# F3-Quad-Brushed-SIDE-USB-JMPR.net
KiCad netlist of a schematic drawn in EAGLE
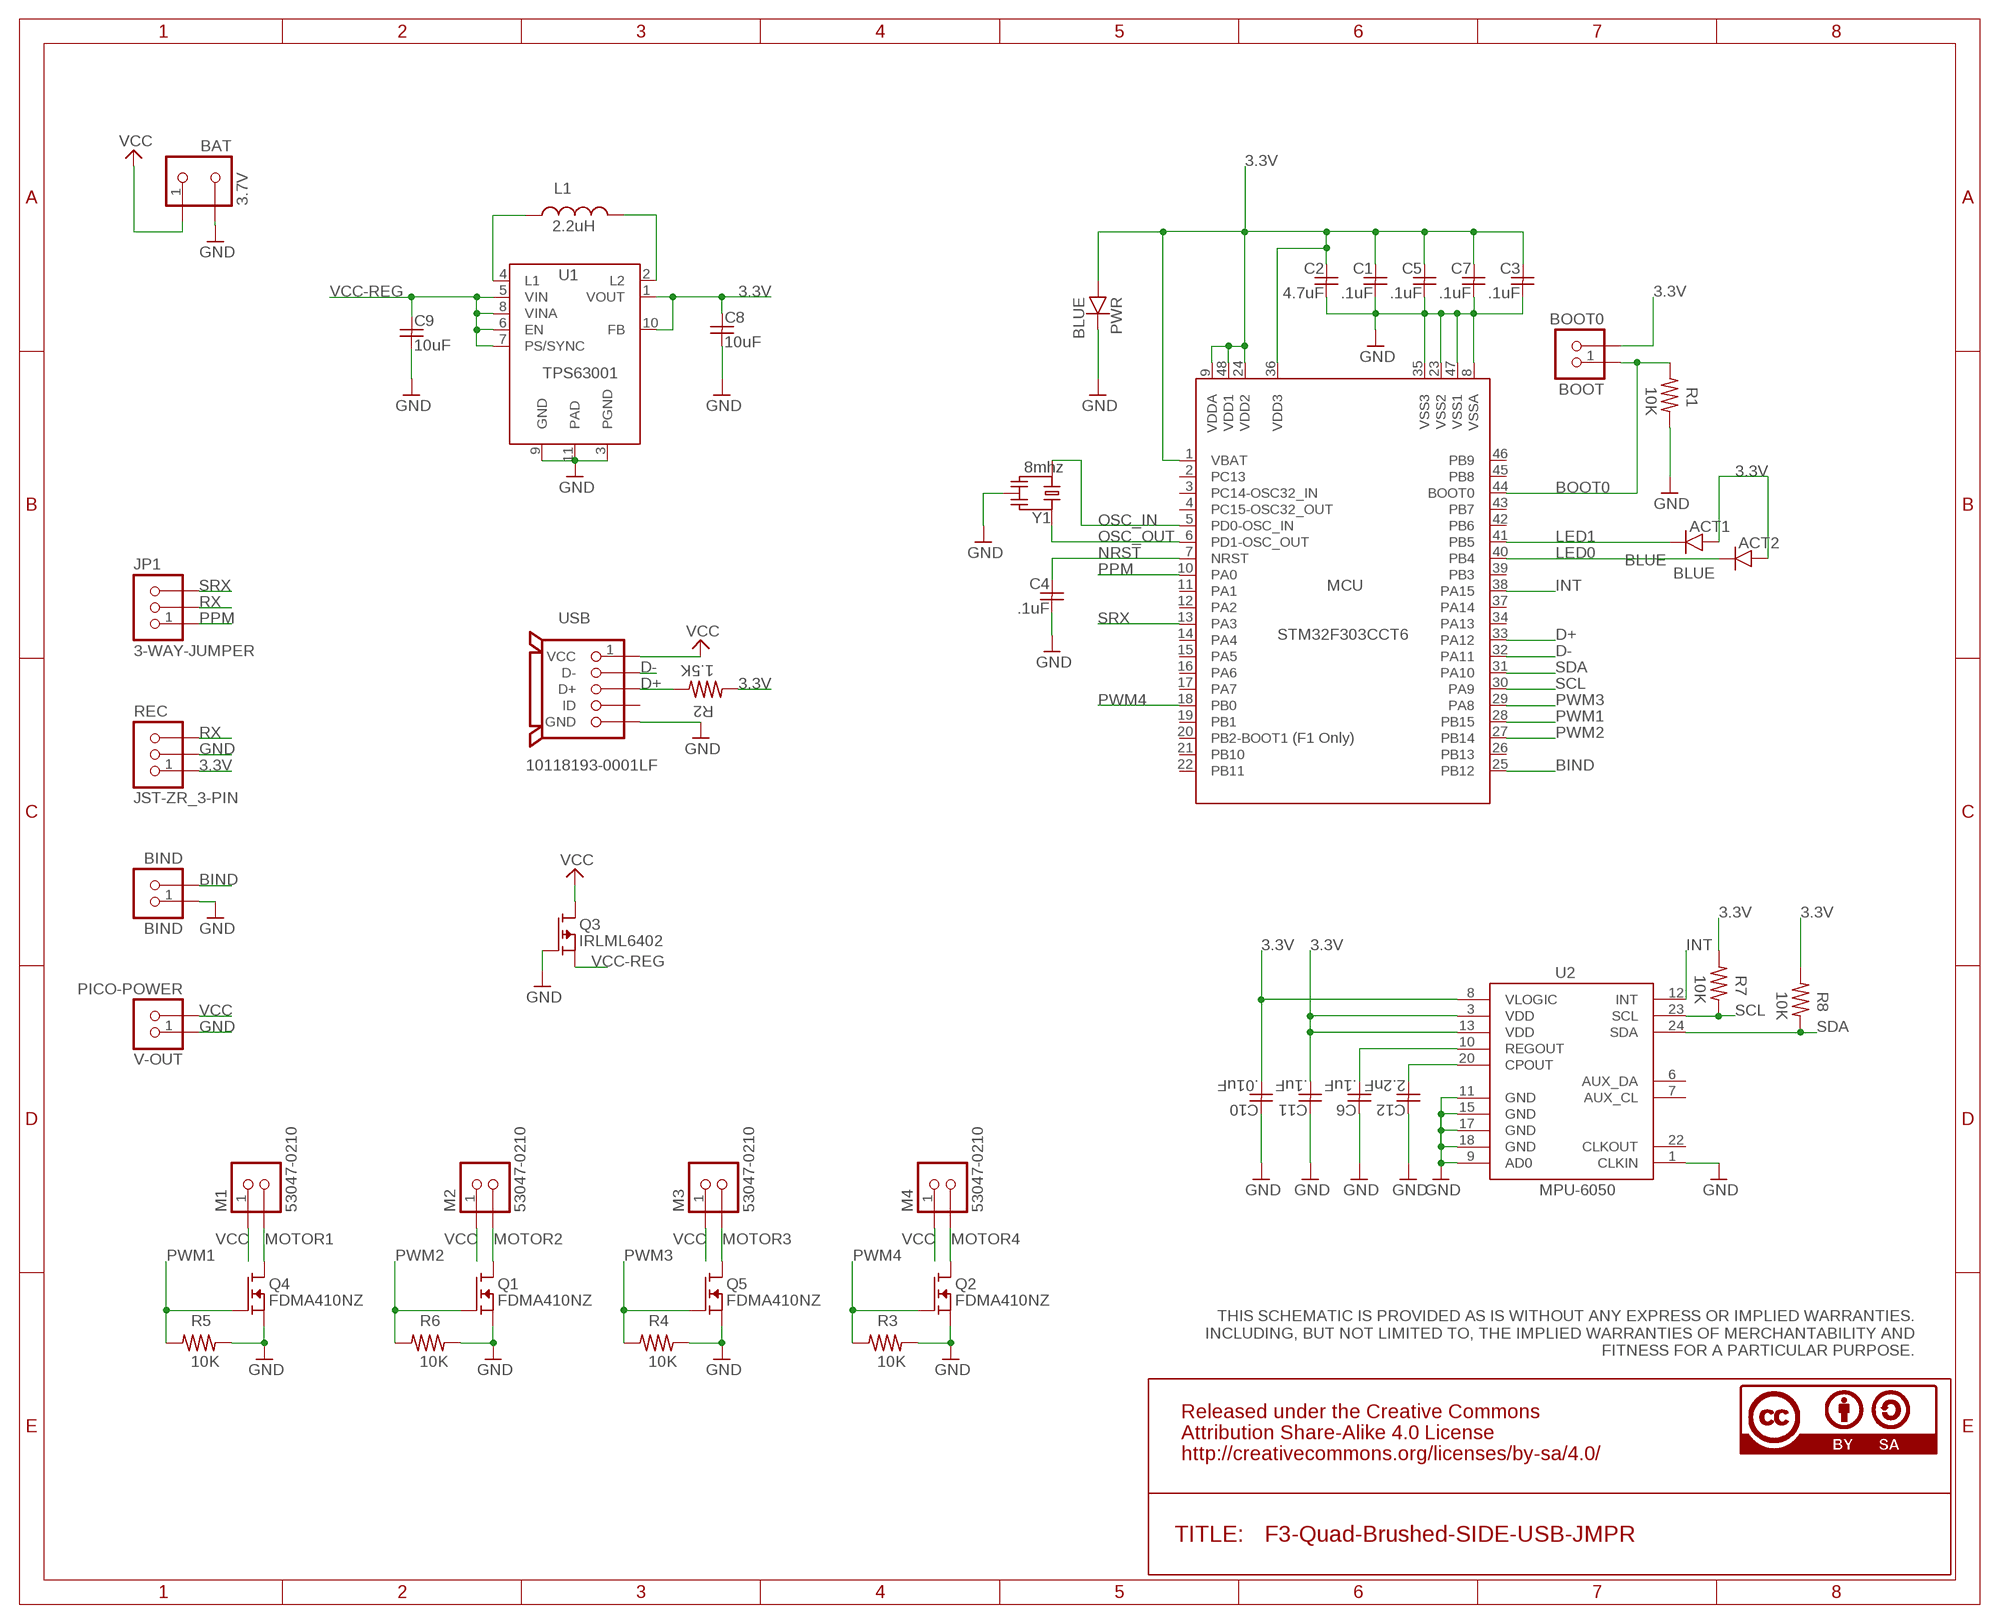
[diagram p0: schematic, sheet 1]

(export (version "E")
  (design (tool "Eeschema 10.0.6"))
  (components
    (comp (ref "ACT1")
      (value "BLUE")
      (footprint "eagle-import:SMD-CHIP-LED-0805")
      (fields (field (name "MF") "Kingbright") (field (name "MPN") "APHCM2012QBC/D-F01"))
      (libsource (lib "eagle-import") (part "SMD-CHIP-LED-0805"))
    )
    (comp (ref "ACT2")
      (value "BLUE")
      (footprint "eagle-import:SMD-CHIP-LED-0805")
      (fields (field (name "MF") "Kingbright") (field (name "MPN") "APHCM2012QBC/D-F01"))
      (libsource (lib "eagle-import") (part "SMD-CHIP-LED-0805"))
    )
    (comp (ref "BAT")
      (value "3.7V")
      (footprint "eagle-import:S2B-PH-K-S")
      (fields (field (name "MF") "JST") (field (name "MPN") "S2B-PH-K-S"))
      (libsource (lib "eagle-import") (part "JST-PH-BAT"))
    )
    (comp (ref "BIND")
      (value "BIND")
      (footprint "eagle-import:1.27MM-PINHEADX2")
      (fields (field (name "MF") "Sullins") (field (name "MPN") "GRPB021VWVN-RC (JUMPER IS M50-1930005)"))
      (libsource (lib "eagle-import") (part "1.27MM-PINHEADX2"))
    )
    (comp (ref "BOOT")
      (value "BOOT0")
      (footprint "eagle-import:1.27MM-PINHEADX2")
      (fields (field (name "MF") "Sullins") (field (name "MPN") "GRPB021VWVN-RC (JUMPER IS M50-1930005)"))
      (libsource (lib "eagle-import") (part "1.27MM-PINHEADX2"))
    )
    (comp (ref "C1")
      (value ".1uF")
      (footprint "eagle-import:MUR-CAP-0603")
      (fields (field (name "MF") "Murata") (field (name "MPN") "GRM188R71C104KA01D"))
      (libsource (lib "eagle-import") (part "CAPACITOR.1UF"))
    )
    (comp (ref "C2")
      (value "4.7uF")
      (footprint "eagle-import:MUR-CAP-0603")
      (fields (field (name "MF") "Murata") (field (name "MPN") "GRJ188C70J475KE11D"))
      (libsource (lib "eagle-import") (part "CAPACITOR4.7UF"))
    )
    (comp (ref "C3")
      (value ".1uF")
      (footprint "eagle-import:MUR-CAP-0603")
      (fields (field (name "MF") "Murata") (field (name "MPN") "GRM188R71C104KA01D"))
      (libsource (lib "eagle-import") (part "CAPACITOR.1UF"))
    )
    (comp (ref "C4")
      (value ".1uF")
      (footprint "eagle-import:MUR-CAP-0603")
      (fields (field (name "MF") "Murata") (field (name "MPN") "GRM188R71C104KA01D"))
      (libsource (lib "eagle-import") (part "CAPACITOR.1UF"))
    )
    (comp (ref "C5")
      (value ".1uF")
      (footprint "eagle-import:MUR-CAP-0603")
      (fields (field (name "MF") "Murata") (field (name "MPN") "GRM188R71C104KA01D"))
      (libsource (lib "eagle-import") (part "CAPACITOR.1UF"))
    )
    (comp (ref "C6")
      (value ".1uF")
      (footprint "eagle-import:MUR-CAP-0603")
      (fields (field (name "MF") "Murata") (field (name "MPN") "GRM188R71C104KA01D"))
      (libsource (lib "eagle-import") (part "CAPACITOR.1UF"))
    )
    (comp (ref "C7")
      (value ".1uF")
      (footprint "eagle-import:MUR-CAP-0603")
      (fields (field (name "MF") "Murata") (field (name "MPN") "GRM188R71C104KA01D"))
      (libsource (lib "eagle-import") (part "CAPACITOR.1UF"))
    )
    (comp (ref "C8")
      (value "10uF")
      (footprint "eagle-import:YUDEN-CAP-0805")
      (fields (field (name "MF") "Taiyo Yuden") (field (name "MPN") "JMK212AB7106KG-T"))
      (libsource (lib "eagle-import") (part "CAPACITOR10UF"))
    )
    (comp (ref "C9")
      (value "10uF")
      (footprint "eagle-import:YUDEN-CAP-0805")
      (fields (field (name "MF") "Taiyo Yuden") (field (name "MPN") "JMK212AB7106KG-T"))
      (libsource (lib "eagle-import") (part "CAPACITOR10UF"))
    )
    (comp (ref "C10")
      (value ".01uF")
      (footprint "eagle-import:MUR-CAP-0603")
      (fields (field (name "MF") "Murata") (field (name "MPN") "GRM188R71C103KA01D"))
      (libsource (lib "eagle-import") (part "CAPACITOR.01UF"))
    )
    (comp (ref "C11")
      (value ".1uF")
      (footprint "eagle-import:MUR-CAP-0603")
      (fields (field (name "MF") "Murata") (field (name "MPN") "GRM188R71C104KA01D"))
      (libsource (lib "eagle-import") (part "CAPACITOR.1UF"))
    )
    (comp (ref "C12")
      (value "2.2nF")
      (footprint "eagle-import:MUR-CAP-0603")
      (fields (field (name "MF") "Murata") (field (name "MPN") "GRM188R71C222KA01D"))
      (libsource (lib "eagle-import") (part "CAPACITOR2.2NF"))
    )
    (comp (ref "JP1")
      (value "3-WAY-JUMPER")
      (footprint "eagle-import:3-WAY-JUMPER")
      (libsource (lib "eagle-import") (part "3-WAY-JUMPER"))
    )
    (comp (ref "L1")
      (value "2.2uH")
      (footprint "eagle-import:NR301X")
      (fields (field (name "MF") "Taiyo Yuden") (field (name "MPN") "NR3015T2R2M"))
      (libsource (lib "eagle-import") (part "NR301X"))
    )
    (comp (ref "M1")
      (value "53047-0210")
      (footprint "eagle-import:PICO-53047-02")
      (fields (field (name "MF") "MOLEX"))
      (libsource (lib "eagle-import") (part "PICO-1.25-MOTOR"))
    )
    (comp (ref "M2")
      (value "53047-0210")
      (footprint "eagle-import:PICO-53047-02")
      (fields (field (name "MF") "MOLEX"))
      (libsource (lib "eagle-import") (part "PICO-1.25-MOTOR"))
    )
    (comp (ref "M3")
      (value "53047-0210")
      (footprint "eagle-import:PICO-53047-02")
      (fields (field (name "MF") "MOLEX"))
      (libsource (lib "eagle-import") (part "PICO-1.25-MOTOR"))
    )
    (comp (ref "M4")
      (value "53047-0210")
      (footprint "eagle-import:PICO-53047-02")
      (fields (field (name "MF") "MOLEX"))
      (libsource (lib "eagle-import") (part "PICO-1.25-MOTOR"))
    )
    (comp (ref "MCU")
      (value "STM32F303CCT6")
      (footprint "eagle-import:LQFP48-7X7")
      (fields (field (name "MF") "ST"))
      (libsource (lib "eagle-import") (part "STM32FX03-F3"))
    )
    (comp (ref "PWR")
      (value "BLUE")
      (footprint "eagle-import:SMD-CHIP-LED-0805")
      (fields (field (name "MF") "Kingbright") (field (name "MPN") "APHCM2012QBC/D-F01"))
      (libsource (lib "eagle-import") (part "SMD-CHIP-LED-0805"))
    )
    (comp (ref "Q1")
      (value "FDMA410NZ")
      (footprint "eagle-import:MICROFET-2X2")
      (fields (field (name "MF") "Fairchild"))
      (libsource (lib "eagle-import") (part "FDMA410NZ"))
    )
    (comp (ref "Q2")
      (value "FDMA410NZ")
      (footprint "eagle-import:MICROFET-2X2")
      (fields (field (name "MF") "Fairchild"))
      (libsource (lib "eagle-import") (part "FDMA410NZ"))
    )
    (comp (ref "Q3")
      (value "IRLML6402")
      (footprint "eagle-import:SOT-23")
      (fields (field (name "MF") "IR"))
      (libsource (lib "eagle-import") (part "MOSFET-P"))
    )
    (comp (ref "Q4")
      (value "FDMA410NZ")
      (footprint "eagle-import:MICROFET-2X2")
      (fields (field (name "MF") "Fairchild"))
      (libsource (lib "eagle-import") (part "FDMA410NZ"))
    )
    (comp (ref "Q5")
      (value "FDMA410NZ")
      (footprint "eagle-import:MICROFET-2X2")
      (fields (field (name "MF") "Fairchild"))
      (libsource (lib "eagle-import") (part "FDMA410NZ"))
    )
    (comp (ref "R1")
      (value "10K")
      (footprint "eagle-import:VISH-RES-0603")
      (fields (field (name "MF") "Vishay") (field (name "MPN") "CRCW060310K0FKEAHP"))
      (libsource (lib "eagle-import") (part "RESISTOR10K"))
    )
    (comp (ref "R2")
      (value "1.5K")
      (footprint "eagle-import:VISH-RES-0603")
      (fields (field (name "MF") "Vishay") (field (name "MPN") "CRCW06031K50FKEAHP"))
      (libsource (lib "eagle-import") (part "RESISTOR1.5K"))
    )
    (comp (ref "R3")
      (value "10K")
      (footprint "eagle-import:VISH-RES-0603")
      (fields (field (name "MF") "Vishay") (field (name "MPN") "CRCW060310K0FKEAHP"))
      (libsource (lib "eagle-import") (part "RESISTOR10K"))
    )
    (comp (ref "R4")
      (value "10K")
      (footprint "eagle-import:VISH-RES-0603")
      (fields (field (name "MF") "Vishay") (field (name "MPN") "CRCW060310K0FKEAHP"))
      (libsource (lib "eagle-import") (part "RESISTOR10K"))
    )
    (comp (ref "R5")
      (value "10K")
      (footprint "eagle-import:VISH-RES-0603")
      (fields (field (name "MF") "Vishay") (field (name "MPN") "CRCW060310K0FKEAHP"))
      (libsource (lib "eagle-import") (part "RESISTOR10K"))
    )
    (comp (ref "R6")
      (value "10K")
      (footprint "eagle-import:VISH-RES-0603")
      (fields (field (name "MF") "Vishay") (field (name "MPN") "CRCW060310K0FKEAHP"))
      (libsource (lib "eagle-import") (part "RESISTOR10K"))
    )
    (comp (ref "R7")
      (value "10K")
      (footprint "eagle-import:VISH-RES-0603")
      (fields (field (name "MF") "Vishay") (field (name "MPN") "CRCW060310K0FKEAHP"))
      (libsource (lib "eagle-import") (part "RESISTOR10K"))
    )
    (comp (ref "R8")
      (value "10K")
      (footprint "eagle-import:VISH-RES-0603")
      (fields (field (name "MF") "Vishay") (field (name "MPN") "CRCW060310K0FKEAHP"))
      (libsource (lib "eagle-import") (part "RESISTOR10K"))
    )
    (comp (ref "REC")
      (value "JST-ZR_3-PIN")
      (footprint "eagle-import:S3B-ZR")
      (fields (field (name "MF") "JST") (field (name "MPN") "S3B-ZR"))
      (libsource (lib "eagle-import") (part "JST-ZR_3-PIN"))
    )
    (comp (ref "U1")
      (value "TPS63001")
      (footprint "eagle-import:VSON-N10")
      (fields (field (name "MF") "TI") (field (name "MPN") "TPS63001DRCR"))
      (libsource (lib "eagle-import") (part "TPS630XX-TPS63001"))
    )
    (comp (ref "U2")
      (value "MPU-6050")
      (footprint "eagle-import:QFN24-4X4")
      (fields (field (name "MF") "Invensense"))
      (libsource (lib "eagle-import") (part "MPU-6050"))
    )
    (comp (ref "USB")
      (value "10118193-0001LF")
      (footprint "eagle-import:10118193-0001LF")
      (fields (field (name "MF") "FCI"))
      (libsource (lib "eagle-import") (part "USB-MICRO-B-FCI"))
    )
    (comp (ref "V-OUT")
      (value "PICO-POWER")
      (footprint "eagle-import:PICO_1.25_.5MM")
      (fields (field (name "MF") "Molex") (field (name "MPN") "53047-0210"))
      (libsource (lib "eagle-import") (part "PICO-POWER"))
    )
    (comp (ref "Y1")
      (value "8mhz")
      (footprint "eagle-import:RESONATOR_8")
      (fields (field (name "MF") "Murata") (field (name "MPN") "CSTCE8M00G55-R0"))
      (libsource (lib "eagle-import") (part "RESONATOR8MHZ"))
    )
  )
  (nets
    (net (code "1") (name "/3.3V") (class "Default")
      (node (ref "ACT1") (pin "A") (pinfunction "A_A") (pintype "passive"))
      (node (ref "ACT2") (pin "A") (pinfunction "A_A") (pintype "passive"))
      (node (ref "BOOT") (pin "2") (pinfunction "2_2") (pintype "passive"))
      (node (ref "C1") (pin "1") (pinfunction "1_1") (pintype "passive"))
      (node (ref "C10") (pin "2") (pinfunction "2_2") (pintype "passive"))
      (node (ref "C11") (pin "2") (pinfunction "2_2") (pintype "passive"))
      (node (ref "C2") (pin "1") (pinfunction "1_1") (pintype "passive"))
      (node (ref "C3") (pin "1") (pinfunction "1_1") (pintype "passive"))
      (node (ref "C5") (pin "1") (pinfunction "1_1") (pintype "passive"))
      (node (ref "C7") (pin "1") (pinfunction "1_1") (pintype "passive"))
      (node (ref "C8") (pin "1") (pinfunction "1_1") (pintype "passive"))
      (node (ref "MCU") (pin "1") (pinfunction "VBAT_1") (pintype "bidirectional"))
      (node (ref "MCU") (pin "24") (pinfunction "VDD2_24") (pintype "bidirectional"))
      (node (ref "MCU") (pin "36") (pinfunction "VDD3_36") (pintype "bidirectional"))
      (node (ref "MCU") (pin "48") (pinfunction "VDD1_48") (pintype "bidirectional"))
      (node (ref "MCU") (pin "9") (pinfunction "VDDA_9") (pintype "bidirectional"))
      (node (ref "PWR") (pin "A") (pinfunction "A_A") (pintype "passive"))
      (node (ref "R2") (pin "2") (pinfunction "2_2") (pintype "passive"))
      (node (ref "R7") (pin "2") (pinfunction "2_2") (pintype "passive"))
      (node (ref "R8") (pin "2") (pinfunction "2_2") (pintype "passive"))
      (node (ref "REC") (pin "1") (pinfunction "1_1") (pintype "bidirectional"))
      (node (ref "U1") (pin "1") (pinfunction "VOUT_1") (pintype "bidirectional"))
      (node (ref "U1") (pin "10") (pinfunction "FB_10") (pintype "bidirectional"))
      (node (ref "U2") (pin "13") (pinfunction "VDD_13") (pintype "bidirectional"))
      (node (ref "U2") (pin "3") (pinfunction "VDD_3") (pintype "bidirectional"))
      (node (ref "U2") (pin "8") (pinfunction "VLOGIC_8") (pintype "bidirectional"))
    )
    (net (code "2") (name "/BIND") (class "Default")
      (node (ref "BIND") (pin "2") (pinfunction "2_2") (pintype "passive"))
      (node (ref "MCU") (pin "25") (pinfunction "PB12_25") (pintype "bidirectional"))
    )
    (net (code "3") (name "/BOOT0") (class "Default")
      (node (ref "BOOT") (pin "1") (pinfunction "1_1") (pintype "passive"))
      (node (ref "MCU") (pin "44") (pinfunction "BOOT0_44") (pintype "bidirectional"))
      (node (ref "R1") (pin "2") (pinfunction "2_2") (pintype "passive"))
    )
    (net (code "4") (name "/D+") (class "Default")
      (node (ref "MCU") (pin "33") (pinfunction "PA12_33") (pintype "bidirectional"))
      (node (ref "R2") (pin "1") (pinfunction "1_1") (pintype "passive"))
      (node (ref "USB") (pin "3") (pinfunction "D+_3") (pintype "passive"))
    )
    (net (code "5") (name "/D-") (class "Default")
      (node (ref "MCU") (pin "32") (pinfunction "PA11_32") (pintype "bidirectional"))
      (node (ref "USB") (pin "2") (pinfunction "D-_2") (pintype "passive"))
    )
    (net (code "6") (name "/INT") (class "Default")
      (node (ref "MCU") (pin "38") (pinfunction "PA15_38") (pintype "bidirectional"))
      (node (ref "U2") (pin "12") (pinfunction "INT_12") (pintype "bidirectional"))
    )
    (net (code "7") (name "/LED0") (class "Default")
      (node (ref "ACT2") (pin "C") (pinfunction "C_C") (pintype "passive"))
      (node (ref "MCU") (pin "40") (pinfunction "PB4_40") (pintype "bidirectional"))
    )
    (net (code "8") (name "/LED1") (class "Default")
      (node (ref "ACT1") (pin "C") (pinfunction "C_C") (pintype "passive"))
      (node (ref "MCU") (pin "41") (pinfunction "PB5_41") (pintype "bidirectional"))
    )
    (net (code "9") (name "/MOTOR1") (class "Default")
      (node (ref "M1") (pin "2") (pinfunction "2_2") (pintype "passive"))
      (node (ref "Q4") (pin "D") (pinfunction "D_D") (pintype "bidirectional"))
      (node (ref "Q4") (pin "D1") (pinfunction "D_D1") (pintype "bidirectional"))
      (node (ref "Q4") (pin "D2") (pinfunction "D_D2") (pintype "bidirectional"))
      (node (ref "Q4") (pin "D3") (pinfunction "D_D3") (pintype "bidirectional"))
      (node (ref "Q4") (pin "D4") (pinfunction "D_D4") (pintype "bidirectional"))
    )
    (net (code "10") (name "/MOTOR2") (class "Default")
      (node (ref "M2") (pin "2") (pinfunction "2_2") (pintype "passive"))
      (node (ref "Q1") (pin "D") (pinfunction "D_D") (pintype "bidirectional"))
      (node (ref "Q1") (pin "D1") (pinfunction "D_D1") (pintype "bidirectional"))
      (node (ref "Q1") (pin "D2") (pinfunction "D_D2") (pintype "bidirectional"))
      (node (ref "Q1") (pin "D3") (pinfunction "D_D3") (pintype "bidirectional"))
      (node (ref "Q1") (pin "D4") (pinfunction "D_D4") (pintype "bidirectional"))
    )
    (net (code "11") (name "/MOTOR3") (class "Default")
      (node (ref "M3") (pin "2") (pinfunction "2_2") (pintype "passive"))
      (node (ref "Q5") (pin "D") (pinfunction "D_D") (pintype "bidirectional"))
      (node (ref "Q5") (pin "D1") (pinfunction "D_D1") (pintype "bidirectional"))
      (node (ref "Q5") (pin "D2") (pinfunction "D_D2") (pintype "bidirectional"))
      (node (ref "Q5") (pin "D3") (pinfunction "D_D3") (pintype "bidirectional"))
      (node (ref "Q5") (pin "D4") (pinfunction "D_D4") (pintype "bidirectional"))
    )
    (net (code "12") (name "/MOTOR4") (class "Default")
      (node (ref "M4") (pin "2") (pinfunction "2_2") (pintype "passive"))
      (node (ref "Q2") (pin "D") (pinfunction "D_D") (pintype "bidirectional"))
      (node (ref "Q2") (pin "D1") (pinfunction "D_D1") (pintype "bidirectional"))
      (node (ref "Q2") (pin "D2") (pinfunction "D_D2") (pintype "bidirectional"))
      (node (ref "Q2") (pin "D3") (pinfunction "D_D3") (pintype "bidirectional"))
      (node (ref "Q2") (pin "D4") (pinfunction "D_D4") (pintype "bidirectional"))
    )
    (net (code "13") (name "/NRST") (class "Default")
      (node (ref "C4") (pin "1") (pinfunction "1_1") (pintype "passive"))
      (node (ref "MCU") (pin "7") (pinfunction "NRST_7") (pintype "bidirectional"))
    )
    (net (code "14") (name "/OSC_IN") (class "Default")
      (node (ref "MCU") (pin "5") (pinfunction "PD0-OSC_IN_5") (pintype "bidirectional"))
      (node (ref "Y1") (pin "3") (pinfunction "3_3") (pintype "passive"))
    )
    (net (code "15") (name "/OSC_OUT") (class "Default")
      (node (ref "MCU") (pin "6") (pinfunction "PD1-OSC_OUT_6") (pintype "bidirectional"))
      (node (ref "Y1") (pin "1") (pinfunction "1_1") (pintype "passive"))
    )
    (net (code "16") (name "/PPM") (class "Default")
      (node (ref "JP1") (pin "1") (pinfunction "1_1") (pintype "bidirectional"))
      (node (ref "MCU") (pin "10") (pinfunction "PA0_10") (pintype "bidirectional"))
    )
    (net (code "17") (name "/PWM1") (class "Default")
      (node (ref "MCU") (pin "28") (pinfunction "PB15_28") (pintype "bidirectional"))
      (node (ref "Q4") (pin "G") (pinfunction "G_G") (pintype "bidirectional"))
      (node (ref "R5") (pin "2") (pinfunction "2_2") (pintype "passive"))
    )
    (net (code "18") (name "/PWM2") (class "Default")
      (node (ref "MCU") (pin "27") (pinfunction "PB14_27") (pintype "bidirectional"))
      (node (ref "Q1") (pin "G") (pinfunction "G_G") (pintype "bidirectional"))
      (node (ref "R6") (pin "2") (pinfunction "2_2") (pintype "passive"))
    )
    (net (code "19") (name "/PWM3") (class "Default")
      (node (ref "MCU") (pin "29") (pinfunction "PA8_29") (pintype "bidirectional"))
      (node (ref "Q5") (pin "G") (pinfunction "G_G") (pintype "bidirectional"))
      (node (ref "R4") (pin "2") (pinfunction "2_2") (pintype "passive"))
    )
    (net (code "20") (name "/PWM4") (class "Default")
      (node (ref "MCU") (pin "18") (pinfunction "PB0_18") (pintype "bidirectional"))
      (node (ref "Q2") (pin "G") (pinfunction "G_G") (pintype "bidirectional"))
      (node (ref "R3") (pin "2") (pinfunction "2_2") (pintype "passive"))
    )
    (net (code "21") (name "/RX") (class "Default")
      (node (ref "JP1") (pin "2") (pinfunction "2_2") (pintype "bidirectional"))
      (node (ref "REC") (pin "3") (pinfunction "3_3") (pintype "bidirectional"))
    )
    (net (code "22") (name "/SCL") (class "Default")
      (node (ref "MCU") (pin "30") (pinfunction "PA9_30") (pintype "bidirectional"))
      (node (ref "R7") (pin "1") (pinfunction "1_1") (pintype "passive"))
      (node (ref "U2") (pin "23") (pinfunction "SCL_23") (pintype "bidirectional"))
    )
    (net (code "23") (name "/SDA") (class "Default")
      (node (ref "MCU") (pin "31") (pinfunction "PA10_31") (pintype "bidirectional"))
      (node (ref "R8") (pin "1") (pinfunction "1_1") (pintype "passive"))
      (node (ref "U2") (pin "24") (pinfunction "SDA_24") (pintype "bidirectional"))
    )
    (net (code "24") (name "/SRX") (class "Default")
      (node (ref "JP1") (pin "3") (pinfunction "3_3") (pintype "bidirectional"))
      (node (ref "MCU") (pin "13") (pinfunction "PA3_13") (pintype "bidirectional"))
    )
    (net (code "25") (name "/VCC-REG") (class "Default")
      (node (ref "C9") (pin "1") (pinfunction "1_1") (pintype "passive"))
      (node (ref "Q3") (pin "2") (pinfunction "S_2") (pintype "bidirectional"))
      (node (ref "U1") (pin "5") (pinfunction "VIN_5") (pintype "bidirectional"))
      (node (ref "U1") (pin "6") (pinfunction "EN_6") (pintype "bidirectional"))
      (node (ref "U1") (pin "7") (pinfunction "PS/SYNC_7") (pintype "bidirectional"))
      (node (ref "U1") (pin "8") (pinfunction "VINA_8") (pintype "bidirectional"))
    )
    (net (code "26") (name "GND") (class "Default")
      (node (ref "BAT") (pin "2") (pinfunction "2_2") (pintype "bidirectional"))
      (node (ref "BIND") (pin "1") (pinfunction "1_1") (pintype "passive"))
      (node (ref "C1") (pin "2") (pinfunction "2_2") (pintype "passive"))
      (node (ref "C10") (pin "1") (pinfunction "1_1") (pintype "passive"))
      (node (ref "C11") (pin "1") (pinfunction "1_1") (pintype "passive"))
      (node (ref "C12") (pin "1") (pinfunction "1_1") (pintype "passive"))
      (node (ref "C2") (pin "2") (pinfunction "2_2") (pintype "passive"))
      (node (ref "C3") (pin "2") (pinfunction "2_2") (pintype "passive"))
      (node (ref "C4") (pin "2") (pinfunction "2_2") (pintype "passive"))
      (node (ref "C5") (pin "2") (pinfunction "2_2") (pintype "passive"))
      (node (ref "C6") (pin "1") (pinfunction "1_1") (pintype "passive"))
      (node (ref "C7") (pin "2") (pinfunction "2_2") (pintype "passive"))
      (node (ref "C8") (pin "2") (pinfunction "2_2") (pintype "passive"))
      (node (ref "C9") (pin "2") (pinfunction "2_2") (pintype "passive"))
      (node (ref "MCU") (pin "23") (pinfunction "VSS2_23") (pintype "bidirectional"))
      (node (ref "MCU") (pin "35") (pinfunction "VSS3_35") (pintype "bidirectional"))
      (node (ref "MCU") (pin "47") (pinfunction "VSS1_47") (pintype "bidirectional"))
      (node (ref "MCU") (pin "8") (pinfunction "VSSA_8") (pintype "bidirectional"))
      (node (ref "PWR") (pin "C") (pinfunction "C_C") (pintype "passive"))
      (node (ref "Q1") (pin "S") (pinfunction "S_S") (pintype "bidirectional"))
      (node (ref "Q1") (pin "S1") (pinfunction "S_S1") (pintype "bidirectional"))
      (node (ref "Q2") (pin "S") (pinfunction "S_S") (pintype "bidirectional"))
      (node (ref "Q2") (pin "S1") (pinfunction "S_S1") (pintype "bidirectional"))
      (node (ref "Q3") (pin "1") (pinfunction "G_1") (pintype "bidirectional"))
      (node (ref "Q4") (pin "S") (pinfunction "S_S") (pintype "bidirectional"))
      (node (ref "Q4") (pin "S1") (pinfunction "S_S1") (pintype "bidirectional"))
      (node (ref "Q5") (pin "S") (pinfunction "S_S") (pintype "bidirectional"))
      (node (ref "Q5") (pin "S1") (pinfunction "S_S1") (pintype "bidirectional"))
      (node (ref "R1") (pin "1") (pinfunction "1_1") (pintype "passive"))
      (node (ref "R3") (pin "1") (pinfunction "1_1") (pintype "passive"))
      (node (ref "R4") (pin "1") (pinfunction "1_1") (pintype "passive"))
      (node (ref "R5") (pin "1") (pinfunction "1_1") (pintype "passive"))
      (node (ref "R6") (pin "1") (pinfunction "1_1") (pintype "passive"))
      (node (ref "REC") (pin "2") (pinfunction "2_2") (pintype "bidirectional"))
      (node (ref "U1") (pin "11") (pinfunction "PAD_11") (pintype "bidirectional"))
      (node (ref "U1") (pin "3") (pinfunction "PGND_3") (pintype "bidirectional"))
      (node (ref "U1") (pin "9") (pinfunction "GND_9") (pintype "bidirectional"))
      (node (ref "U2") (pin "1") (pinfunction "CLKIN_1") (pintype "bidirectional"))
      (node (ref "U2") (pin "11") (pinfunction "GND_11") (pintype "bidirectional"))
      (node (ref "U2") (pin "15") (pinfunction "GND_15") (pintype "bidirectional"))
      (node (ref "U2") (pin "17") (pinfunction "GND_17") (pintype "bidirectional"))
      (node (ref "U2") (pin "18") (pinfunction "GND_18") (pintype "bidirectional"))
      (node (ref "U2") (pin "9") (pinfunction "AD0_9") (pintype "bidirectional"))
      (node (ref "USB") (pin "5") (pinfunction "GND_5") (pintype "passive"))
      (node (ref "USB") (pin "GND") (pinfunction "GND_GND") (pintype "passive"))
      (node (ref "USB") (pin "GND2") (pinfunction "GND_GND2") (pintype "passive"))
      (node (ref "USB") (pin "HOLE1") (pinfunction "GND_HOLE1") (pintype "passive"))
      (node (ref "USB") (pin "HOLE2") (pinfunction "GND_HOLE2") (pintype "passive"))
      (node (ref "V-OUT") (pin "1") (pinfunction "1_1") (pintype "passive"))
      (node (ref "Y1") (pin "2") (pinfunction "2_2") (pintype "passive"))
    )
    (net (code "27") (name "Net-(U1-L1)") (class "Default")
      (node (ref "L1") (pin "1") (pinfunction "1_1") (pintype "passive"))
      (node (ref "U1") (pin "4") (pinfunction "L1_4") (pintype "bidirectional"))
    )
    (net (code "28") (name "Net-(U1-L2)") (class "Default")
      (node (ref "L1") (pin "2") (pinfunction "2_2") (pintype "passive"))
      (node (ref "U1") (pin "2") (pinfunction "L2_2") (pintype "bidirectional"))
    )
    (net (code "29") (name "Net-(U2-CPOUT)") (class "Default")
      (node (ref "C12") (pin "2") (pinfunction "2_2") (pintype "passive"))
      (node (ref "U2") (pin "20") (pinfunction "CPOUT_20") (pintype "bidirectional"))
    )
    (net (code "30") (name "Net-(U2-REGOUT)") (class "Default")
      (node (ref "C6") (pin "2") (pinfunction "2_2") (pintype "passive"))
      (node (ref "U2") (pin "10") (pinfunction "REGOUT_10") (pintype "bidirectional"))
    )
    (net (code "31") (name "VCC") (class "Default")
      (node (ref "BAT") (pin "1") (pinfunction "1_1") (pintype "bidirectional"))
      (node (ref "M1") (pin "1") (pinfunction "1_1") (pintype "passive"))
      (node (ref "M2") (pin "1") (pinfunction "1_1") (pintype "passive"))
      (node (ref "M3") (pin "1") (pinfunction "1_1") (pintype "passive"))
      (node (ref "M4") (pin "1") (pinfunction "1_1") (pintype "passive"))
      (node (ref "Q3") (pin "3") (pinfunction "D_3") (pintype "bidirectional"))
      (node (ref "USB") (pin "1") (pinfunction "VCC_1") (pintype "passive"))
      (node (ref "V-OUT") (pin "2") (pinfunction "2_2") (pintype "passive"))
    )
    (net (code "32") (name "unconnected-(MCU-PA1-Pad11)") (class "Default")
      (node (ref "MCU") (pin "11") (pinfunction "PA1_11") (pintype "bidirectional"))
    )
    (net (code "33") (name "unconnected-(MCU-PA2-Pad12)") (class "Default")
      (node (ref "MCU") (pin "12") (pinfunction "PA2_12") (pintype "bidirectional"))
    )
    (net (code "34") (name "unconnected-(MCU-PA4-Pad14)") (class "Default")
      (node (ref "MCU") (pin "14") (pinfunction "PA4_14") (pintype "bidirectional"))
    )
    (net (code "35") (name "unconnected-(MCU-PA5-Pad15)") (class "Default")
      (node (ref "MCU") (pin "15") (pinfunction "PA5_15") (pintype "bidirectional"))
    )
    (net (code "36") (name "unconnected-(MCU-PA6-Pad16)") (class "Default")
      (node (ref "MCU") (pin "16") (pinfunction "PA6_16") (pintype "bidirectional"))
    )
    (net (code "37") (name "unconnected-(MCU-PA7-Pad17)") (class "Default")
      (node (ref "MCU") (pin "17") (pinfunction "PA7_17") (pintype "bidirectional"))
    )
    (net (code "38") (name "unconnected-(MCU-PA13-Pad34)") (class "Default")
      (node (ref "MCU") (pin "34") (pinfunction "PA13_34") (pintype "bidirectional"))
    )
    (net (code "39") (name "unconnected-(MCU-PA14-Pad37)") (class "Default")
      (node (ref "MCU") (pin "37") (pinfunction "PA14_37") (pintype "bidirectional"))
    )
    (net (code "40") (name "unconnected-(MCU-PB1-Pad19)") (class "Default")
      (node (ref "MCU") (pin "19") (pinfunction "PB1_19") (pintype "bidirectional"))
    )
    (net (code "41") (name "unconnected-(MCU-PB2-BOOT1-Pad20)") (class "Default")
      (node (ref "MCU") (pin "20") (pinfunction "PB2-BOOT1_20") (pintype "bidirectional"))
    )
    (net (code "42") (name "unconnected-(MCU-PB3-Pad39)") (class "Default")
      (node (ref "MCU") (pin "39") (pinfunction "PB3_39") (pintype "bidirectional"))
    )
    (net (code "43") (name "unconnected-(MCU-PB6-Pad42)") (class "Default")
      (node (ref "MCU") (pin "42") (pinfunction "PB6_42") (pintype "bidirectional"))
    )
    (net (code "44") (name "unconnected-(MCU-PB7-Pad43)") (class "Default")
      (node (ref "MCU") (pin "43") (pinfunction "PB7_43") (pintype "bidirectional"))
    )
    (net (code "45") (name "unconnected-(MCU-PB8-Pad45)") (class "Default")
      (node (ref "MCU") (pin "45") (pinfunction "PB8_45") (pintype "bidirectional"))
    )
    (net (code "46") (name "unconnected-(MCU-PB9-Pad46)") (class "Default")
      (node (ref "MCU") (pin "46") (pinfunction "PB9_46") (pintype "bidirectional"))
    )
    (net (code "47") (name "unconnected-(MCU-PB10-Pad21)") (class "Default")
      (node (ref "MCU") (pin "21") (pinfunction "PB10_21") (pintype "bidirectional"))
    )
    (net (code "48") (name "unconnected-(MCU-PB11-Pad22)") (class "Default")
      (node (ref "MCU") (pin "22") (pinfunction "PB11_22") (pintype "bidirectional"))
    )
    (net (code "49") (name "unconnected-(MCU-PB13-Pad26)") (class "Default")
      (node (ref "MCU") (pin "26") (pinfunction "PB13_26") (pintype "bidirectional"))
    )
    (net (code "50") (name "unconnected-(MCU-PC13-Pad2)") (class "Default")
      (node (ref "MCU") (pin "2") (pinfunction "PC13_2") (pintype "bidirectional"))
    )
    (net (code "51") (name "unconnected-(MCU-PC14-OSC32_IN-Pad3)") (class "Default")
      (node (ref "MCU") (pin "3") (pinfunction "PC14-OSC32_IN_3") (pintype "bidirectional"))
    )
    (net (code "52") (name "unconnected-(MCU-PC15-OSC32_OUT-Pad4)") (class "Default")
      (node (ref "MCU") (pin "4") (pinfunction "PC15-OSC32_OUT_4") (pintype "bidirectional"))
    )
    (net (code "53") (name "unconnected-(U2-AUX_CL-Pad7)") (class "Default")
      (node (ref "U2") (pin "7") (pinfunction "AUX_CL_7") (pintype "bidirectional"))
    )
    (net (code "54") (name "unconnected-(U2-AUX_DA-Pad6)") (class "Default")
      (node (ref "U2") (pin "6") (pinfunction "AUX_DA_6") (pintype "bidirectional"))
    )
    (net (code "55") (name "unconnected-(U2-CLKOUT-Pad22)") (class "Default")
      (node (ref "U2") (pin "22") (pinfunction "CLKOUT_22") (pintype "bidirectional"))
    )
    (net (code "56") (name "unconnected-(USB-ID-Pad4)") (class "Default")
      (node (ref "USB") (pin "4") (pinfunction "ID_4") (pintype "passive"))
    )
  )
)
